# LED_connector.net
KiCad netlist of a schematic drawn in Altium Designer
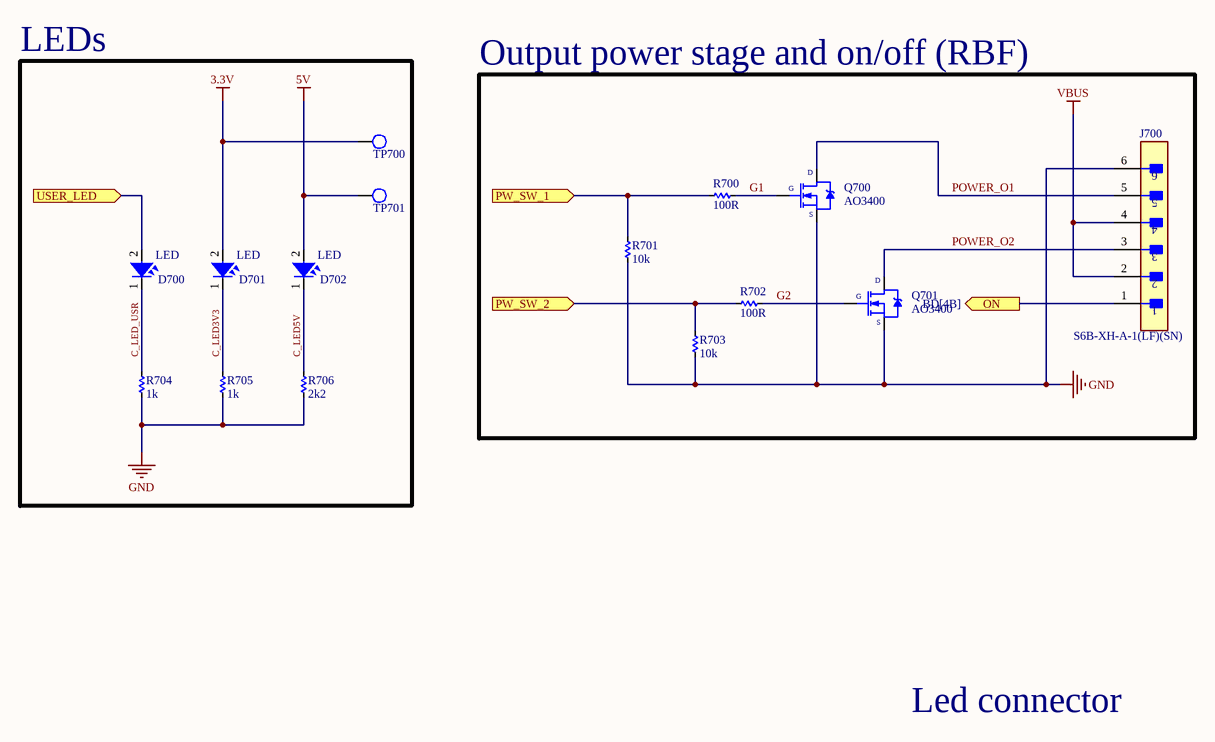
[diagram p0: LED connector.SchDoc]

(export (version "E")
  (design (tool "Eeschema 10.0.6"))
  (components
    (comp (ref "D700")
      (value "LED")
      (footprint "LED-0805-Green")
      (libsource (lib "Library") (part "LED SMD"))
    )
    (comp (ref "D701")
      (value "LED")
      (footprint "LED-0805-Green")
      (libsource (lib "Library") (part "LED SMD"))
    )
    (comp (ref "D702")
      (value "LED")
      (footprint "LED-0805-Green")
      (libsource (lib "Library") (part "LED SMD"))
    )
    (comp (ref "J700")
      (value "S6B-XH-A-1(LF)(SN)")
      (footprint "FP-S6B-XH-A-1_LF_SN-MFG")
      (description "CONN HEADER R/A P6OS 2.5MM")
      (libsource (lib "Altium Content Vault") (part "f2cb566baf1c37ab5a3b8e90bbeafd6"))
    )
    (comp (ref "Q700")
      (value "AO3400")
      (footprint "SOT23-123")
      (description "N-MOS 30V 5.8A")
      (libsource (lib "Library") (part "AO3400"))
    )
    (comp (ref "Q701")
      (value "AO3400")
      (footprint "SOT23-123")
      (description "N-MOS 30V 5.8A")
      (libsource (lib "Library") (part "AO3400"))
    )
    (comp (ref "R700")
      (value "100R")
      (footprint "RES-SMD-0603")
      (description "Resistor")
      (fields
        (field (name "MANUFACTURER") "Generic Components")
        (field (name "PUBLISHER") "Altium Hobart Technology Centre")
      )
      (libsource (lib "Library") (part "Res-SMD"))
    )
    (comp (ref "R701")
      (value "10k")
      (footprint "RES-SMD-0603")
      (description "Resistor")
      (fields
        (field (name "MANUFACTURER") "Generic Components")
        (field (name "PUBLISHER") "Altium Hobart Technology Centre")
      )
      (libsource (lib "Library") (part "Res-SMD"))
    )
    (comp (ref "R702")
      (value "100R")
      (footprint "RES-SMD-0603")
      (description "Resistor")
      (fields
        (field (name "MANUFACTURER") "Generic Components")
        (field (name "PUBLISHER") "Altium Hobart Technology Centre")
      )
      (libsource (lib "Library") (part "Res-SMD"))
    )
    (comp (ref "R703")
      (value "10k")
      (footprint "RES-SMD-0603")
      (description "Resistor")
      (fields
        (field (name "MANUFACTURER") "Generic Components")
        (field (name "PUBLISHER") "Altium Hobart Technology Centre")
      )
      (libsource (lib "Library") (part "Res-SMD"))
    )
    (comp (ref "R704")
      (value "1k")
      (footprint "RES-SMD-0603")
      (description "Resistor")
      (fields
        (field (name "MANUFACTURER") "Generic Components")
        (field (name "PUBLISHER") "Altium Hobart Technology Centre")
      )
      (libsource (lib "Library") (part "Res-SMD"))
    )
    (comp (ref "R705")
      (value "1k")
      (footprint "RES-SMD-0603")
      (description "Resistor")
      (fields
        (field (name "MANUFACTURER") "Generic Components")
        (field (name "PUBLISHER") "Altium Hobart Technology Centre")
      )
      (libsource (lib "Library") (part "Res-SMD"))
    )
    (comp (ref "R706")
      (value "2k2")
      (footprint "RES-SMD-0603")
      (description "Resistor")
      (fields
        (field (name "MANUFACTURER") "Generic Components")
        (field (name "PUBLISHER") "Altium Hobart Technology Centre")
      )
      (libsource (lib "Library") (part "Res-SMD"))
    )
    (comp (ref "TP700")
      (value "Test-Point")
      (footprint "TESTPOINT")
      (libsource (lib "Library") (part "Test-Point"))
    )
    (comp (ref "TP701")
      (value "Test-Point")
      (footprint "TESTPOINT")
      (libsource (lib "Library") (part "Test-Point"))
    )
  )
  (nets
    (net (code "1") (name "/C_LED3V3") (class "Default")
      (node (ref "D701") (pin "2") (pinfunction "2_2") (pintype "passive"))
      (node (ref "R705") (pin "1") (pinfunction "1_1") (pintype "passive"))
    )
    (net (code "2") (name "/C_LED5V") (class "Default")
      (node (ref "D702") (pin "2") (pinfunction "2_2") (pintype "passive"))
      (node (ref "R706") (pin "1") (pinfunction "1_1") (pintype "passive"))
    )
    (net (code "3") (name "/C_LED_USR") (class "Default")
      (node (ref "D700") (pin "2") (pinfunction "2_2") (pintype "passive"))
      (node (ref "R704") (pin "1") (pinfunction "1_1") (pintype "passive"))
    )
    (net (code "4") (name "/G1") (class "Default")
      (node (ref "Q700") (pin "1") (pinfunction "G_1") (pintype "passive"))
      (node (ref "R700") (pin "1") (pinfunction "1_1") (pintype "passive"))
    )
    (net (code "5") (name "/G2") (class "Default")
      (node (ref "Q701") (pin "1") (pinfunction "G_1") (pintype "passive"))
      (node (ref "R702") (pin "1") (pinfunction "1_1") (pintype "passive"))
    )
    (net (code "6") (name "/ON") (class "Default")
      (node (ref "J700") (pin "1") (pinfunction "1_1") (pintype "passive"))
    )
    (net (code "7") (name "/POWER_O1") (class "Default")
      (node (ref "J700") (pin "5") (pinfunction "5_5") (pintype "passive"))
      (node (ref "Q700") (pin "2") (pinfunction "D_2") (pintype "passive"))
    )
    (net (code "8") (name "/POWER_O2") (class "Default")
      (node (ref "J700") (pin "3") (pinfunction "3_3") (pintype "passive"))
      (node (ref "Q701") (pin "2") (pinfunction "D_2") (pintype "passive"))
    )
    (net (code "9") (name "/PW_SW_1") (class "Default")
      (node (ref "R700") (pin "2") (pinfunction "2_2") (pintype "passive"))
      (node (ref "R701") (pin "1") (pinfunction "1_1") (pintype "passive"))
    )
    (net (code "10") (name "/PW_SW_2") (class "Default")
      (node (ref "R702") (pin "2") (pinfunction "2_2") (pintype "passive"))
      (node (ref "R703") (pin "1") (pinfunction "1_1") (pintype "passive"))
    )
    (net (code "11") (name "/USER_LED") (class "Default")
      (node (ref "D700") (pin "1") (pinfunction "1_1") (pintype "passive"))
    )
    (net (code "12") (name "3.3V") (class "Default")
      (node (ref "D701") (pin "1") (pinfunction "1_1") (pintype "passive"))
      (node (ref "TP700") (pin "1") (pinfunction "1_1") (pintype "passive"))
    )
    (net (code "13") (name "5V") (class "Default")
      (node (ref "D702") (pin "1") (pinfunction "1_1") (pintype "passive"))
      (node (ref "TP701") (pin "1") (pinfunction "1_1") (pintype "passive"))
    )
    (net (code "14") (name "GND") (class "Default")
      (node (ref "J700") (pin "6") (pinfunction "6_6") (pintype "passive"))
      (node (ref "Q700") (pin "3") (pinfunction "S_3") (pintype "passive"))
      (node (ref "Q701") (pin "3") (pinfunction "S_3") (pintype "passive"))
      (node (ref "R701") (pin "2") (pinfunction "2_2") (pintype "passive"))
      (node (ref "R703") (pin "2") (pinfunction "2_2") (pintype "passive"))
      (node (ref "R704") (pin "2") (pinfunction "2_2") (pintype "passive"))
      (node (ref "R705") (pin "2") (pinfunction "2_2") (pintype "passive"))
      (node (ref "R706") (pin "2") (pinfunction "2_2") (pintype "passive"))
    )
    (net (code "15") (name "VBUS") (class "Default")
      (node (ref "J700") (pin "2") (pinfunction "2_2") (pintype "passive"))
      (node (ref "J700") (pin "4") (pinfunction "4_4") (pintype "passive"))
    )
  )
)
